# Nodino-Core.net
KiCad netlist of a schematic drawn in EAGLE
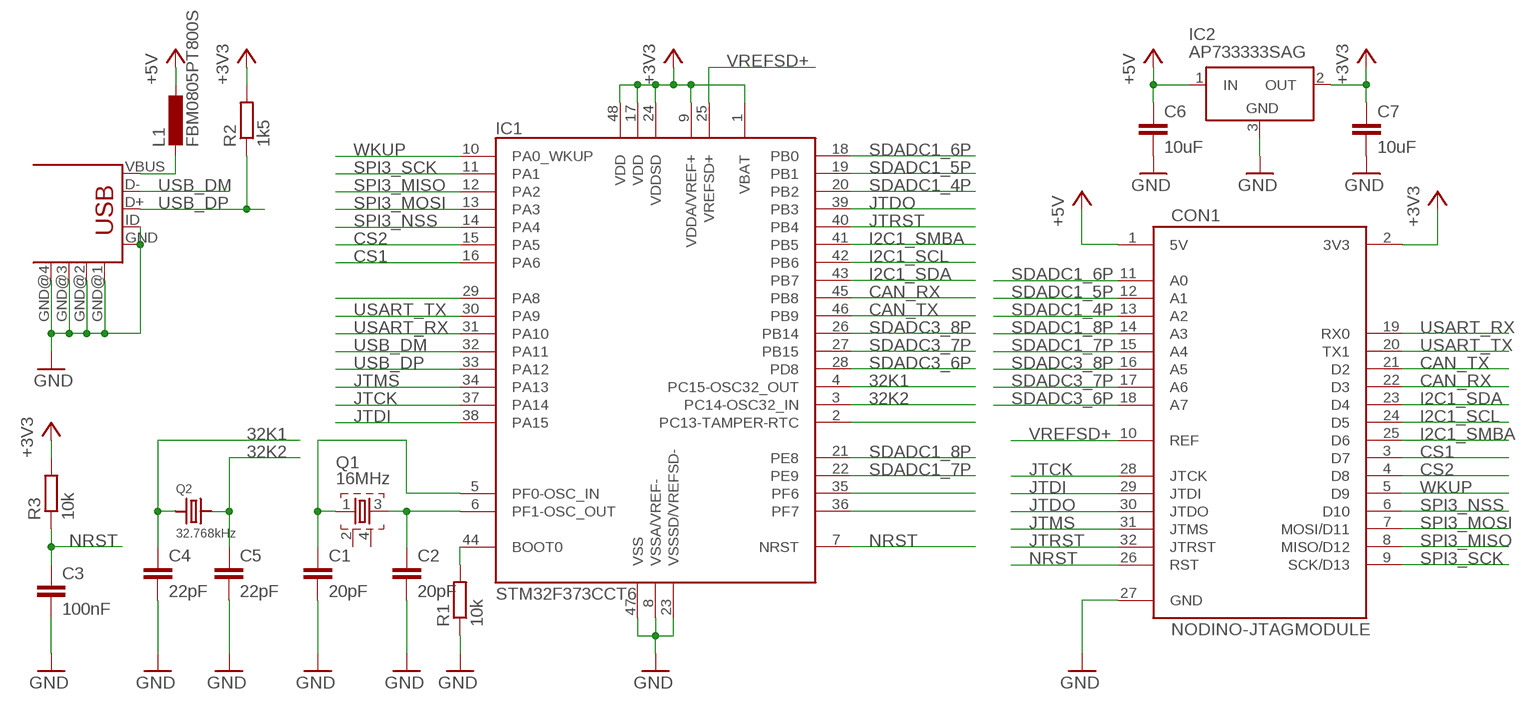
[diagram p0: schematic, sheet 1]

(export (version "E")
  (design (tool "Eeschema 10.0.6"))
  (components
    (comp (ref "C1")
      (value "20pF")
      (footprint "eagle-import:C0603K")
      (libsource (lib "eagle-import") (part "C-EUC0603K"))
    )
    (comp (ref "C2")
      (value "20pF")
      (footprint "eagle-import:C0603K")
      (libsource (lib "eagle-import") (part "C-EUC0603K"))
    )
    (comp (ref "C3")
      (value "100nF")
      (footprint "eagle-import:C0603K")
      (libsource (lib "eagle-import") (part "C-EUC0603K"))
    )
    (comp (ref "C4")
      (value "22pF")
      (footprint "eagle-import:C0603K")
      (libsource (lib "eagle-import") (part "C-EUC0603K"))
    )
    (comp (ref "C5")
      (value "22pF")
      (footprint "eagle-import:C0603K")
      (libsource (lib "eagle-import") (part "C-EUC0603K"))
    )
    (comp (ref "C6")
      (value "10uF")
      (footprint "eagle-import:C0603K")
      (libsource (lib "eagle-import") (part "C-EUC0603K"))
    )
    (comp (ref "C7")
      (value "10uF")
      (footprint "eagle-import:C0603K")
      (libsource (lib "eagle-import") (part "C-EUC0603K"))
    )
    (comp (ref "CON1")
      (value "NODINO-JTAGMODULE")
      (footprint "eagle-import:NODINO-JTAG-MOD")
      (libsource (lib "eagle-import") (part "NODINO-JTAGMODULE"))
    )
    (comp (ref "CON2")
      (value "USB-OTG_SHIELD")
      (footprint "eagle-import:USB-UAB-S1")
      (libsource (lib "eagle-import") (part "USB-OTG_SHIELD"))
    )
    (comp (ref "IC1")
      (value "STM32F373CCT6")
      (footprint "eagle-import:LQFP48")
      (libsource (lib "eagle-import") (part "STM32F373CCT6"))
    )
    (comp (ref "IC2")
      (value "AP733333SAG")
      (footprint "eagle-import:SOT23")
      (libsource (lib "eagle-import") (part "AP733333SAG"))
    )
    (comp (ref "L1")
      (value "FBM0805PT800S")
      (footprint "eagle-import:L0805")
      (libsource (lib "eagle-import") (part "L-EUL0805"))
    )
    (comp (ref "Q1")
      (value "16MHz")
      (footprint "eagle-import:FA-20H")
      (libsource (lib "eagle-import") (part "FA-20H"))
    )
    (comp (ref "Q2")
      (value "32.768kHz")
      (footprint "eagle-import:ABS07")
      (libsource (lib "eagle-import") (part "CRYSTAL.ABS07"))
    )
    (comp (ref "R1")
      (value "10k")
      (footprint "eagle-import:R0603K")
      (libsource (lib "eagle-import") (part "R-EU_R0603K"))
    )
    (comp (ref "R2")
      (value "1k5")
      (footprint "eagle-import:R0603K")
      (libsource (lib "eagle-import") (part "R-EU_R0603K"))
    )
    (comp (ref "R3")
      (value "10k")
      (footprint "eagle-import:R0603K")
      (libsource (lib "eagle-import") (part "R-EU_R0603K"))
    )
  )
  (nets
    (net (code "1") (name "+3V3") (class "Default")
      (node (ref "C7") (pin "1") (pinfunction "1_1") (pintype "passive"))
      (node (ref "CON1") (pin "2") (pinfunction "3V3_2") (pintype "bidirectional"))
      (node (ref "IC1") (pin "1") (pinfunction "VBAT_1") (pintype "power_in"))
      (node (ref "IC1") (pin "17") (pinfunction "VDD_17") (pintype "power_in"))
      (node (ref "IC1") (pin "24") (pinfunction "VDDSD_24") (pintype "power_in"))
      (node (ref "IC1") (pin "48") (pinfunction "VDD_48") (pintype "power_in"))
      (node (ref "IC1") (pin "9") (pinfunction "VDDA/VREF+_9") (pintype "power_in"))
      (node (ref "IC2") (pin "2") (pinfunction "OUT_2") (pintype "output"))
      (node (ref "R2") (pin "2") (pinfunction "2_2") (pintype "passive"))
      (node (ref "R3") (pin "2") (pinfunction "2_2") (pintype "passive"))
    )
    (net (code "2") (name "+5V") (class "Default")
      (node (ref "C6") (pin "1") (pinfunction "1_1") (pintype "passive"))
      (node (ref "CON1") (pin "1") (pinfunction "5V_1") (pintype "bidirectional"))
      (node (ref "IC2") (pin "1") (pinfunction "IN_1") (pintype "input"))
      (node (ref "L1") (pin "1") (pinfunction "1_1") (pintype "passive"))
    )
    (net (code "3") (name "/32K1") (class "Default")
      (node (ref "C4") (pin "1") (pinfunction "1_1") (pintype "passive"))
      (node (ref "IC1") (pin "4") (pinfunction "PC15-OSC32_OUT_4") (pintype "input"))
      (node (ref "Q2") (pin "1") (pinfunction "1_1") (pintype "passive"))
    )
    (net (code "4") (name "/32K2") (class "Default")
      (node (ref "C5") (pin "1") (pinfunction "1_1") (pintype "passive"))
      (node (ref "IC1") (pin "3") (pinfunction "PC14-OSC32_IN_3") (pintype "input"))
      (node (ref "Q2") (pin "2") (pinfunction "2_2") (pintype "passive"))
    )
    (net (code "5") (name "/CAN_RX") (class "Default")
      (node (ref "CON1") (pin "22") (pinfunction "D3_22") (pintype "bidirectional"))
      (node (ref "IC1") (pin "45") (pinfunction "PB8_45") (pintype "bidirectional"))
    )
    (net (code "6") (name "/CAN_TX") (class "Default")
      (node (ref "CON1") (pin "21") (pinfunction "D2_21") (pintype "bidirectional"))
      (node (ref "IC1") (pin "46") (pinfunction "PB9_46") (pintype "input"))
    )
    (net (code "7") (name "/CS1") (class "Default")
      (node (ref "CON1") (pin "3") (pinfunction "D7_3") (pintype "bidirectional"))
      (node (ref "IC1") (pin "16") (pinfunction "PA6_16") (pintype "bidirectional"))
    )
    (net (code "8") (name "/CS2") (class "Default")
      (node (ref "CON1") (pin "4") (pinfunction "D8_4") (pintype "bidirectional"))
      (node (ref "IC1") (pin "15") (pinfunction "PA5_15") (pintype "bidirectional"))
    )
    (net (code "9") (name "/I2C1_SCL") (class "Default")
      (node (ref "CON1") (pin "24") (pinfunction "D5_24") (pintype "bidirectional"))
      (node (ref "IC1") (pin "42") (pinfunction "PB6_42") (pintype "input"))
    )
    (net (code "10") (name "/I2C1_SDA") (class "Default")
      (node (ref "CON1") (pin "23") (pinfunction "D4_23") (pintype "bidirectional"))
      (node (ref "IC1") (pin "43") (pinfunction "PB7_43") (pintype "bidirectional"))
    )
    (net (code "11") (name "/I2C1_SMBA") (class "Default")
      (node (ref "CON1") (pin "25") (pinfunction "D6_25") (pintype "bidirectional"))
      (node (ref "IC1") (pin "41") (pinfunction "PB5_41") (pintype "input"))
    )
    (net (code "12") (name "/JTCK") (class "Default")
      (node (ref "CON1") (pin "28") (pinfunction "JTCK_28") (pintype "bidirectional"))
      (node (ref "IC1") (pin "37") (pinfunction "PA14_37") (pintype "bidirectional"))
    )
    (net (code "13") (name "/JTDI") (class "Default")
      (node (ref "CON1") (pin "29") (pinfunction "JTDI_29") (pintype "bidirectional"))
      (node (ref "IC1") (pin "38") (pinfunction "PA15_38") (pintype "bidirectional"))
    )
    (net (code "14") (name "/JTDO") (class "Default")
      (node (ref "CON1") (pin "30") (pinfunction "JTDO_30") (pintype "bidirectional"))
      (node (ref "IC1") (pin "39") (pinfunction "PB3_39") (pintype "bidirectional"))
    )
    (net (code "15") (name "/JTMS") (class "Default")
      (node (ref "CON1") (pin "31") (pinfunction "JTMS_31") (pintype "bidirectional"))
      (node (ref "IC1") (pin "34") (pinfunction "PA13_34") (pintype "bidirectional"))
    )
    (net (code "16") (name "/JTRST") (class "Default")
      (node (ref "CON1") (pin "32") (pinfunction "JTRST_32") (pintype "bidirectional"))
      (node (ref "IC1") (pin "40") (pinfunction "PB4_40") (pintype "bidirectional"))
    )
    (net (code "17") (name "/NRST") (class "Default")
      (node (ref "C3") (pin "1") (pinfunction "1_1") (pintype "passive"))
      (node (ref "CON1") (pin "26") (pinfunction "RST_26") (pintype "bidirectional"))
      (node (ref "IC1") (pin "7") (pinfunction "NRST_7") (pintype "input"))
      (node (ref "R3") (pin "1") (pinfunction "1_1") (pintype "passive"))
    )
    (net (code "18") (name "/SDADC1_4P") (class "Default")
      (node (ref "CON1") (pin "13") (pinfunction "A2_13") (pintype "bidirectional"))
      (node (ref "IC1") (pin "20") (pinfunction "PB2_20") (pintype "bidirectional"))
    )
    (net (code "19") (name "/SDADC1_5P") (class "Default")
      (node (ref "CON1") (pin "12") (pinfunction "A1_12") (pintype "bidirectional"))
      (node (ref "IC1") (pin "19") (pinfunction "PB1_19") (pintype "bidirectional"))
    )
    (net (code "20") (name "/SDADC1_6P") (class "Default")
      (node (ref "CON1") (pin "11") (pinfunction "A0_11") (pintype "bidirectional"))
      (node (ref "IC1") (pin "18") (pinfunction "PB0_18") (pintype "bidirectional"))
    )
    (net (code "21") (name "/SDADC1_7P") (class "Default")
      (node (ref "CON1") (pin "15") (pinfunction "A4_15") (pintype "bidirectional"))
      (node (ref "IC1") (pin "22") (pinfunction "PE9_22") (pintype "input"))
    )
    (net (code "22") (name "/SDADC1_8P") (class "Default")
      (node (ref "CON1") (pin "14") (pinfunction "A3_14") (pintype "bidirectional"))
      (node (ref "IC1") (pin "21") (pinfunction "PE8_21") (pintype "input"))
    )
    (net (code "23") (name "/SDADC3_6P") (class "Default")
      (node (ref "CON1") (pin "18") (pinfunction "A7_18") (pintype "bidirectional"))
      (node (ref "IC1") (pin "28") (pinfunction "PD8_28") (pintype "input"))
    )
    (net (code "24") (name "/SDADC3_7P") (class "Default")
      (node (ref "CON1") (pin "17") (pinfunction "A6_17") (pintype "bidirectional"))
      (node (ref "IC1") (pin "27") (pinfunction "PB15_27") (pintype "input"))
    )
    (net (code "25") (name "/SDADC3_8P") (class "Default")
      (node (ref "CON1") (pin "16") (pinfunction "A5_16") (pintype "bidirectional"))
      (node (ref "IC1") (pin "26") (pinfunction "PB14_26") (pintype "bidirectional"))
    )
    (net (code "26") (name "/SPI3_MISO") (class "Default")
      (node (ref "CON1") (pin "8") (pinfunction "MISO/D12_8") (pintype "bidirectional"))
      (node (ref "IC1") (pin "12") (pinfunction "PA2_12") (pintype "bidirectional"))
    )
    (net (code "27") (name "/SPI3_MOSI") (class "Default")
      (node (ref "CON1") (pin "7") (pinfunction "MOSI/D11_7") (pintype "bidirectional"))
      (node (ref "IC1") (pin "13") (pinfunction "PA3_13") (pintype "bidirectional"))
    )
    (net (code "28") (name "/SPI3_NSS") (class "Default")
      (node (ref "CON1") (pin "6") (pinfunction "D10_6") (pintype "bidirectional"))
      (node (ref "IC1") (pin "14") (pinfunction "PA4_14") (pintype "bidirectional"))
    )
    (net (code "29") (name "/SPI3_SCK") (class "Default")
      (node (ref "CON1") (pin "9") (pinfunction "SCK/D13_9") (pintype "bidirectional"))
      (node (ref "IC1") (pin "11") (pinfunction "PA1_11") (pintype "bidirectional"))
    )
    (net (code "30") (name "/USART_RX") (class "Default")
      (node (ref "CON1") (pin "19") (pinfunction "RX0_19") (pintype "bidirectional"))
      (node (ref "IC1") (pin "31") (pinfunction "PA10_31") (pintype "bidirectional"))
    )
    (net (code "31") (name "/USART_TX") (class "Default")
      (node (ref "CON1") (pin "20") (pinfunction "TX1_20") (pintype "bidirectional"))
      (node (ref "IC1") (pin "30") (pinfunction "PA9_30") (pintype "input"))
    )
    (net (code "32") (name "/USB_DM") (class "Default")
      (node (ref "CON2") (pin "D-") (pinfunction "D-_D-") (pintype "bidirectional"))
      (node (ref "IC1") (pin "32") (pinfunction "PA11_32") (pintype "bidirectional"))
    )
    (net (code "33") (name "/USB_DP") (class "Default")
      (node (ref "CON2") (pin "D+") (pinfunction "D+_D+") (pintype "bidirectional"))
      (node (ref "IC1") (pin "33") (pinfunction "PA12_33") (pintype "bidirectional"))
      (node (ref "R2") (pin "1") (pinfunction "1_1") (pintype "passive"))
    )
    (net (code "34") (name "/VREFSD+") (class "Default")
      (node (ref "CON1") (pin "10") (pinfunction "REF_10") (pintype "bidirectional"))
      (node (ref "IC1") (pin "25") (pinfunction "VREFSD+_25") (pintype "power_in"))
    )
    (net (code "35") (name "/WKUP") (class "Default")
      (node (ref "CON1") (pin "5") (pinfunction "D9_5") (pintype "bidirectional"))
      (node (ref "IC1") (pin "10") (pinfunction "PA0_WKUP_10") (pintype "bidirectional"))
    )
    (net (code "36") (name "GND") (class "Default")
      (node (ref "C1") (pin "2") (pinfunction "2_2") (pintype "passive"))
      (node (ref "C2") (pin "2") (pinfunction "2_2") (pintype "passive"))
      (node (ref "C3") (pin "2") (pinfunction "2_2") (pintype "passive"))
      (node (ref "C4") (pin "2") (pinfunction "2_2") (pintype "passive"))
      (node (ref "C5") (pin "2") (pinfunction "2_2") (pintype "passive"))
      (node (ref "C6") (pin "2") (pinfunction "2_2") (pintype "passive"))
      (node (ref "C7") (pin "2") (pinfunction "2_2") (pintype "passive"))
      (node (ref "CON1") (pin "27") (pinfunction "GND_27") (pintype "bidirectional"))
      (node (ref "CON2") (pin "GND") (pinfunction "GND_GND") (pintype "power_in"))
      (node (ref "CON2") (pin "GND@1") (pinfunction "GND_GND@1") (pintype "power_in"))
      (node (ref "CON2") (pin "GND@2") (pinfunction "GND_GND@2") (pintype "power_in"))
      (node (ref "CON2") (pin "GND@3") (pinfunction "GND_GND@3") (pintype "power_in"))
      (node (ref "CON2") (pin "GND@4") (pinfunction "GND_GND@4") (pintype "power_in"))
      (node (ref "CON2") (pin "ID") (pinfunction "ID_ID") (pintype "bidirectional"))
      (node (ref "IC1") (pin "23") (pinfunction "VSSSD/VREFSD-_23") (pintype "power_in"))
      (node (ref "IC1") (pin "47") (pinfunction "VSS_47") (pintype "power_in"))
      (node (ref "IC1") (pin "8") (pinfunction "VSSA/VREF-_8") (pintype "power_in"))
      (node (ref "IC2") (pin "3") (pinfunction "GND_3") (pintype "power_in"))
      (node (ref "R1") (pin "1") (pinfunction "1_1") (pintype "passive"))
    )
    (net (code "37") (name "Net-(CON2-PadVBUS)") (class "Default")
      (node (ref "CON2") (pin "VBUS") (pinfunction "VBUS_VBUS") (pintype "power_in"))
      (node (ref "L1") (pin "2") (pinfunction "2_2") (pintype "passive"))
    )
    (net (code "38") (name "Net-(IC1-BOOT0)") (class "Default")
      (node (ref "IC1") (pin "44") (pinfunction "BOOT0_44") (pintype "input"))
      (node (ref "R1") (pin "2") (pinfunction "2_2") (pintype "passive"))
    )
    (net (code "39") (name "Net-(IC1-PF0-OSC_IN)") (class "Default")
      (node (ref "C1") (pin "1") (pinfunction "1_1") (pintype "passive"))
      (node (ref "IC1") (pin "5") (pinfunction "PF0-OSC_IN_5") (pintype "input"))
      (node (ref "Q1") (pin "1") (pinfunction "1_1") (pintype "passive"))
    )
    (net (code "40") (name "Net-(IC1-PF1-OSC_OUT)") (class "Default")
      (node (ref "C2") (pin "1") (pinfunction "1_1") (pintype "passive"))
      (node (ref "IC1") (pin "6") (pinfunction "PF1-OSC_OUT_6") (pintype "input"))
      (node (ref "Q1") (pin "3") (pinfunction "3_3") (pintype "passive"))
    )
    (net (code "41") (name "unconnected-(IC1-PA8-Pad29)") (class "Default")
      (node (ref "IC1") (pin "29") (pinfunction "PA8_29") (pintype "bidirectional"))
    )
    (net (code "42") (name "unconnected-(IC1-PC13-TAMPER-RTC-Pad2)") (class "Default")
      (node (ref "IC1") (pin "2") (pinfunction "PC13-TAMPER-RTC_2") (pintype "input"))
    )
    (net (code "43") (name "unconnected-(IC1-PF6-Pad35)") (class "Default")
      (node (ref "IC1") (pin "35") (pinfunction "PF6_35") (pintype "input"))
    )
    (net (code "44") (name "unconnected-(IC1-PF7-Pad36)") (class "Default")
      (node (ref "IC1") (pin "36") (pinfunction "PF7_36") (pintype "input"))
    )
    (net (code "45") (name "unconnected-(Q1-Pad2)") (class "Default")
      (node (ref "Q1") (pin "2") (pinfunction "2_2") (pintype "passive"))
    )
    (net (code "46") (name "unconnected-(Q1-Pad4)") (class "Default")
      (node (ref "Q1") (pin "4") (pinfunction "4_4") (pintype "passive"))
    )
  )
)
